# Sheet1.net
KiCad netlist of a schematic drawn in Altium Designer
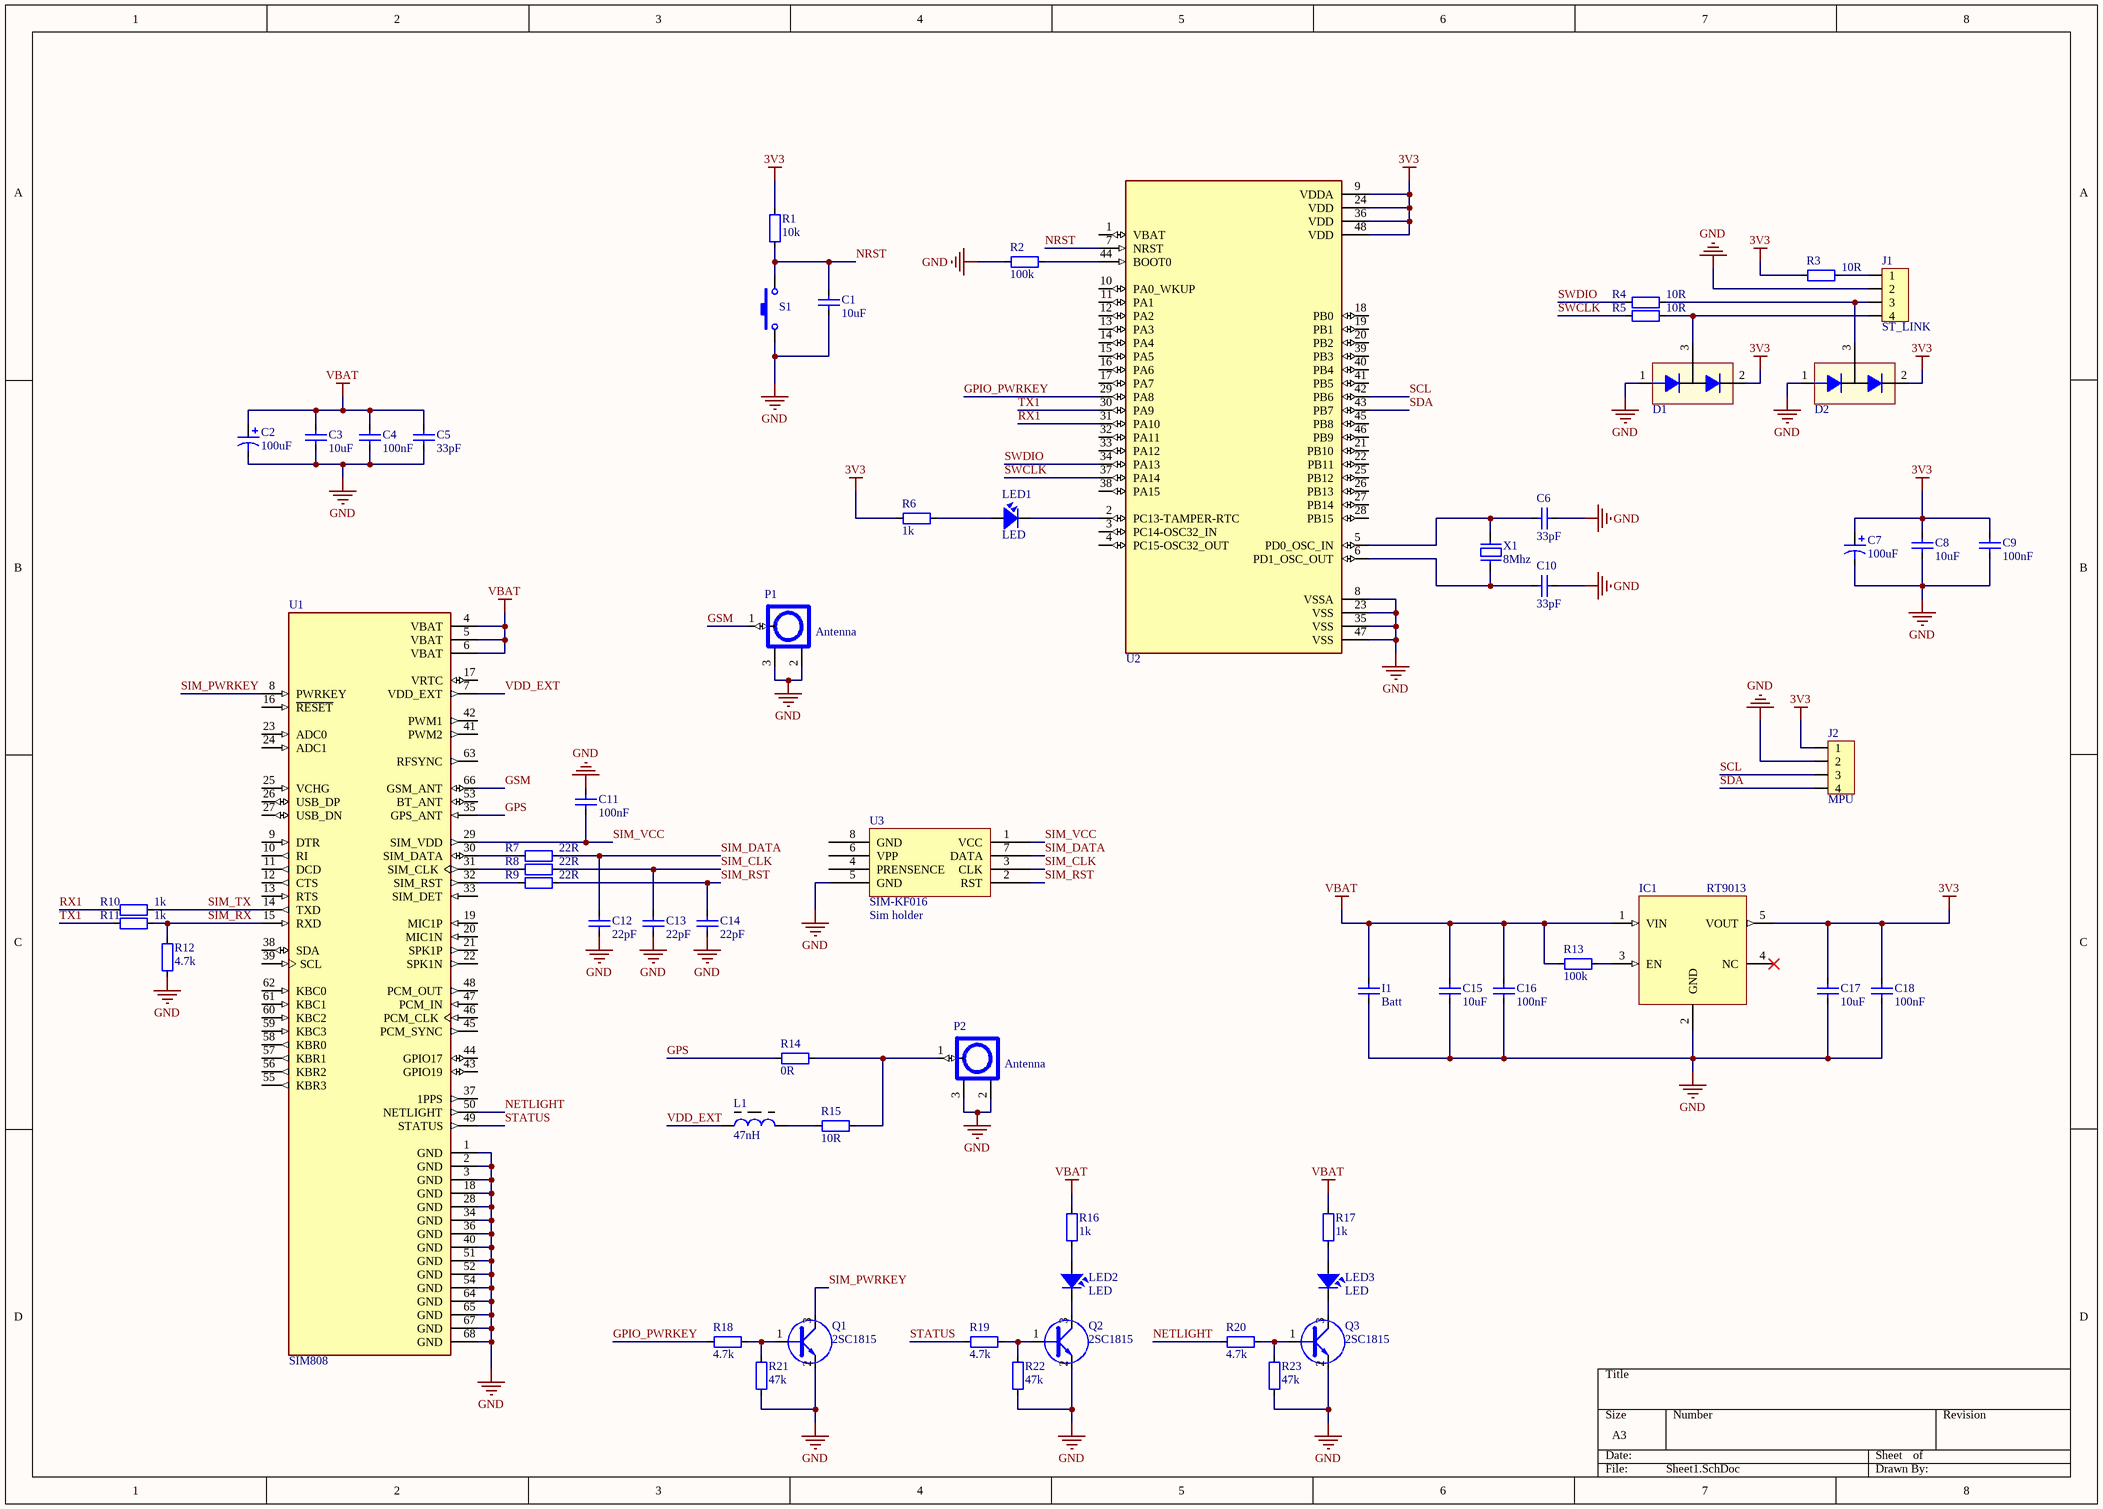
[diagram p0: Sheet1.SchDoc]

(export (version "E")
  (design (tool "Eeschema 10.0.6"))
  (components
    (comp (ref "C1")
      (value "10uF")
      (footprint "CAP_0603")
      (description "Capacitor")
      (fields (field (name "PUBLISHER") "Altium Limited"))
      (libsource (lib "My Library") (part "CapSMD"))
    )
    (comp (ref "C2")
      (value "100uF")
      (footprint "CAP_7343")
      (description "Tantalum")
      (fields (field (name "PUBLISHER") "Altium Limited"))
      (libsource (lib "My Library") (part "Cap Pol"))
    )
    (comp (ref "C3")
      (value "10uF")
      (footprint "CAP_0603")
      (description "Capacitor")
      (fields (field (name "PUBLISHER") "Altium Limited"))
      (libsource (lib "My Library") (part "CapSMD"))
    )
    (comp (ref "C4")
      (value "100nF")
      (footprint "CAP_0603")
      (description "Capacitor")
      (fields (field (name "PUBLISHER") "Altium Limited"))
      (libsource (lib "My Library") (part "CapSMD"))
    )
    (comp (ref "C5")
      (value "33pF")
      (footprint "CAP_0603")
      (description "Capacitor")
      (fields (field (name "PUBLISHER") "Altium Limited"))
      (libsource (lib "My Library") (part "CapSMD"))
    )
    (comp (ref "C6")
      (value "33pF")
      (footprint "CAP_0603")
      (description "Capacitor")
      (fields (field (name "PUBLISHER") "Altium Limited"))
      (libsource (lib "My Library") (part "CapSMD"))
    )
    (comp (ref "C7")
      (value "100uF")
      (footprint "CAP_7343")
      (description "Tantalum")
      (fields (field (name "PUBLISHER") "Altium Limited"))
      (libsource (lib "My Library") (part "Cap Pol"))
    )
    (comp (ref "C8")
      (value "10uF")
      (footprint "CAP_0603")
      (description "Capacitor")
      (fields (field (name "PUBLISHER") "Altium Limited"))
      (libsource (lib "My Library") (part "CapSMD"))
    )
    (comp (ref "C9")
      (value "100nF")
      (footprint "CAP_0603")
      (description "Capacitor")
      (fields (field (name "PUBLISHER") "Altium Limited"))
      (libsource (lib "My Library") (part "CapSMD"))
    )
    (comp (ref "C10")
      (value "33pF")
      (footprint "CAP_0603")
      (description "Capacitor")
      (fields (field (name "PUBLISHER") "Altium Limited"))
      (libsource (lib "My Library") (part "CapSMD"))
    )
    (comp (ref "C11")
      (value "100nF")
      (footprint "CAP_0603")
      (description "Capacitor")
      (fields (field (name "PUBLISHER") "Altium Limited"))
      (libsource (lib "My Library") (part "CapSMD"))
    )
    (comp (ref "C12")
      (value "22pF")
      (footprint "CAP_0603")
      (description "Capacitor")
      (fields (field (name "PUBLISHER") "Altium Limited"))
      (libsource (lib "My Library") (part "CapSMD"))
    )
    (comp (ref "C13")
      (value "22pF")
      (footprint "CAP_0603")
      (description "Capacitor")
      (fields (field (name "PUBLISHER") "Altium Limited"))
      (libsource (lib "My Library") (part "CapSMD"))
    )
    (comp (ref "C14")
      (value "22pF")
      (footprint "CAP_0603")
      (description "Capacitor")
      (fields (field (name "PUBLISHER") "Altium Limited"))
      (libsource (lib "My Library") (part "CapSMD"))
    )
    (comp (ref "C15")
      (value "10uF")
      (footprint "CAP_0603")
      (description "Capacitor")
      (fields (field (name "PUBLISHER") "Altium Limited"))
      (libsource (lib "My Library") (part "CapSMD"))
    )
    (comp (ref "C16")
      (value "100nF")
      (footprint "CAP_0603")
      (description "Capacitor")
      (fields (field (name "PUBLISHER") "Altium Limited"))
      (libsource (lib "My Library") (part "CapSMD"))
    )
    (comp (ref "C17")
      (value "10uF")
      (footprint "CAP_0603")
      (description "Capacitor")
      (fields (field (name "PUBLISHER") "Altium Limited"))
      (libsource (lib "My Library") (part "CapSMD"))
    )
    (comp (ref "C18")
      (value "100nF")
      (footprint "CAP_0603")
      (description "Capacitor")
      (fields (field (name "PUBLISHER") "Altium Limited"))
      (libsource (lib "My Library") (part "CapSMD"))
    )
    (comp (ref "D1")
      (value "DIODE-BAV99")
      (footprint "SOT23")
      (description "ZENER, SOT23,")
      (fields
        (field (name "MANUFACTURER") "ON Semiconductor / Fairchild")
        (field (name "MANUFACTURER PART NUMBER") "BAV99")
        (field (name ".CREATOR") "LeKhaLinh")
        (field (name ".CHECKPCB") "LeKhaLinh")
        (field (name ".CHECKSCH") "LeKhaLinh")
      )
      (libsource (lib "GPS_Traking_V1_1") (part "DIODE-BAV99"))
    )
    (comp (ref "D2")
      (value "DIODE-BAV99")
      (footprint "SOT23")
      (description "ZENER, SOT23,")
      (fields
        (field (name "MANUFACTURER") "ON Semiconductor / Fairchild")
        (field (name "MANUFACTURER PART NUMBER") "BAV99")
        (field (name ".CREATOR") "LeKhaLinh")
        (field (name ".CHECKPCB") "LeKhaLinh")
        (field (name ".CHECKSCH") "LeKhaLinh")
      )
      (libsource (lib "GPS_Traking_V1_1") (part "DIODE-BAV99"))
    )
    (comp (ref "I1")
      (value "Batt")
      (footprint "CAP_3216")
      (description "Pad")
      (fields (field (name "PUBLISHER") "Altium Limited"))
      (libsource (lib "My Library") (part "CapSMD"))
    )
    (comp (ref "IC1")
      (value "RT9013")
      (footprint "SOT23-5")
      (description "RT9013-33GB IC REG LINEAR 3.3V 500mA SOT23-5")
      (libsource (lib "My Library") (part "RT9013"))
    )
    (comp (ref "J1")
      (value "ST_LINK")
      (footprint "JP4-D1T")
      (description "Header IDC, 4 x 1 Pin Vertical 2.54mm Pitch (Non-Boxed, Male)")
      (fields
        (field (name "MANUFACTURER") "Würth Elektronik eiSos GmbH")
        (field (name "PARTNO") "613002143121")
        (field (name "CREATED BY") "Karrer Zheng")
      )
      (libsource (lib "My Library") (part "Header4"))
    )
    (comp (ref "J2")
      (value "MPU")
      (footprint "JP4-D1T")
      (description "Header IDC, 4 x 1 Pin Vertical 2.54mm Pitch (Non-Boxed, Male)")
      (fields
        (field (name "MANUFACTURER") "Würth Elektronik eiSos GmbH")
        (field (name "PARTNO") "613002143121")
        (field (name "CREATED BY") "Karrer Zheng")
      )
      (libsource (lib "My Library") (part "Header4"))
    )
    (comp (ref "L1")
      (value "47nH")
      (footprint "L-0805")
      (description "Inductor")
      (libsource (lib "My Library") (part "Inductor Ferit"))
    )
    (comp (ref "LED1")
      (value "LED")
      (footprint "LED-0805-Orange")
      (description "LED Single colour Green and Red")
      (libsource (lib "My Library") (part "LED"))
    )
    (comp (ref "LED2")
      (value "LED")
      (footprint "LED-0805-Yellow")
      (description "LED Single colour Green and Red")
      (libsource (lib "My Library") (part "LED"))
    )
    (comp (ref "LED3")
      (value "LED")
      (footprint "LED-0805-Red")
      (description "LED Single colour Green and Red")
      (libsource (lib "My Library") (part "LED"))
    )
    (comp (ref "P1")
      (value "Antenna")
      (footprint "IPXS")
      (description "Antenna GSM GPS")
      (libsource (lib "My Library") (part "IPXSx66"))
    )
    (comp (ref "P2")
      (value "Antenna")
      (footprint "IPXS")
      (description "Antenna GSM GPS")
      (libsource (lib "My Library") (part "IPXSx66"))
    )
    (comp (ref "Q1")
      (value "2SC1815")
      (footprint "SOT23D")
      (description "NPN 600mW, ECB")
      (libsource (lib "My Library") (part "2SC1815"))
    )
    (comp (ref "Q2")
      (value "2SC1815")
      (footprint "SOT23D")
      (description "NPN 600mW, ECB")
      (libsource (lib "My Library") (part "2SC1815"))
    )
    (comp (ref "Q3")
      (value "2SC1815")
      (footprint "SOT23D")
      (description "NPN 600mW, ECB")
      (libsource (lib "My Library") (part "2SC1815"))
    )
    (comp (ref "R1")
      (value "10k")
      (footprint "RES-SMD-0603")
      (description "Resistor")
      (fields
        (field (name "MANUFACTURER") "Generic Components")
        (field (name "PUBLISHER") "Altium Hobart Technology Centre")
      )
      (libsource (lib "My Library") (part "Resistor - SMD"))
    )
    (comp (ref "R2")
      (value "100k")
      (footprint "RES-SMD-0603")
      (description "Resistor")
      (fields
        (field (name "MANUFACTURER") "Generic Components")
        (field (name "PUBLISHER") "Altium Hobart Technology Centre")
      )
      (libsource (lib "My Library") (part "Resistor - SMD"))
    )
    (comp (ref "R3")
      (value "10R")
      (footprint "RES-SMD-0603")
      (description "Resistor")
      (fields
        (field (name "MANUFACTURER") "Generic Components")
        (field (name "PUBLISHER") "Altium Hobart Technology Centre")
      )
      (libsource (lib "My Library") (part "Resistor - SMD"))
    )
    (comp (ref "R4")
      (value "10R")
      (footprint "RES-SMD-0603")
      (description "Resistor")
      (fields
        (field (name "MANUFACTURER") "Generic Components")
        (field (name "PUBLISHER") "Altium Hobart Technology Centre")
      )
      (libsource (lib "My Library") (part "Resistor - SMD"))
    )
    (comp (ref "R5")
      (value "10R")
      (footprint "RES-SMD-0603")
      (description "Resistor")
      (fields
        (field (name "MANUFACTURER") "Generic Components")
        (field (name "PUBLISHER") "Altium Hobart Technology Centre")
      )
      (libsource (lib "My Library") (part "Resistor - SMD"))
    )
    (comp (ref "R6")
      (value "1k")
      (footprint "RES-SMD-0603")
      (description "Resistor")
      (fields
        (field (name "MANUFACTURER") "Generic Components")
        (field (name "PUBLISHER") "Altium Hobart Technology Centre")
      )
      (libsource (lib "My Library") (part "Resistor - SMD"))
    )
    (comp (ref "R7")
      (value "22R")
      (footprint "RES-SMD-0603")
      (description "Resistor")
      (fields
        (field (name "MANUFACTURER") "Generic Components")
        (field (name "PUBLISHER") "Altium Hobart Technology Centre")
      )
      (libsource (lib "My Library") (part "Resistor - SMD"))
    )
    (comp (ref "R8")
      (value "22R")
      (footprint "RES-SMD-0603")
      (description "Resistor")
      (fields
        (field (name "MANUFACTURER") "Generic Components")
        (field (name "PUBLISHER") "Altium Hobart Technology Centre")
      )
      (libsource (lib "My Library") (part "Resistor - SMD"))
    )
    (comp (ref "R9")
      (value "22R")
      (footprint "RES-SMD-0603")
      (description "Resistor")
      (fields
        (field (name "MANUFACTURER") "Generic Components")
        (field (name "PUBLISHER") "Altium Hobart Technology Centre")
      )
      (libsource (lib "My Library") (part "Resistor - SMD"))
    )
    (comp (ref "R10")
      (value "1k")
      (footprint "RES-SMD-0603")
      (description "Resistor")
      (fields
        (field (name "MANUFACTURER") "Generic Components")
        (field (name "PUBLISHER") "Altium Hobart Technology Centre")
      )
      (libsource (lib "My Library") (part "Resistor - SMD"))
    )
    (comp (ref "R11")
      (value "1k")
      (footprint "RES-SMD-0603")
      (description "Resistor")
      (fields
        (field (name "MANUFACTURER") "Generic Components")
        (field (name "PUBLISHER") "Altium Hobart Technology Centre")
      )
      (libsource (lib "My Library") (part "Resistor - SMD"))
    )
    (comp (ref "R12")
      (value "4.7k")
      (footprint "RES-SMD-0603")
      (description "Resistor")
      (fields
        (field (name "MANUFACTURER") "Generic Components")
        (field (name "PUBLISHER") "Altium Hobart Technology Centre")
      )
      (libsource (lib "My Library") (part "Resistor - SMD"))
    )
    (comp (ref "R13")
      (value "100k")
      (footprint "RES-SMD-0603")
      (description "Resistor")
      (fields
        (field (name "MANUFACTURER") "Generic Components")
        (field (name "PUBLISHER") "Altium Hobart Technology Centre")
      )
      (libsource (lib "My Library") (part "Resistor - SMD"))
    )
    (comp (ref "R14")
      (value "0R")
      (footprint "RES-SMD-0805")
      (description "Resistor")
      (fields
        (field (name "MANUFACTURER") "Generic Components")
        (field (name "PUBLISHER") "Altium Hobart Technology Centre")
      )
      (libsource (lib "My Library") (part "Resistor - SMD"))
    )
    (comp (ref "R15")
      (value "10R")
      (footprint "RES-SMD-0805")
      (description "Resistor")
      (fields
        (field (name "MANUFACTURER") "Generic Components")
        (field (name "PUBLISHER") "Altium Hobart Technology Centre")
      )
      (libsource (lib "My Library") (part "Resistor - SMD"))
    )
    (comp (ref "R16")
      (value "1k")
      (footprint "RES-SMD-0603")
      (description "Resistor")
      (fields
        (field (name "MANUFACTURER") "Generic Components")
        (field (name "PUBLISHER") "Altium Hobart Technology Centre")
      )
      (libsource (lib "My Library") (part "Resistor - SMD"))
    )
    (comp (ref "R17")
      (value "1k")
      (footprint "RES-SMD-0603")
      (description "Resistor")
      (fields
        (field (name "MANUFACTURER") "Generic Components")
        (field (name "PUBLISHER") "Altium Hobart Technology Centre")
      )
      (libsource (lib "My Library") (part "Resistor - SMD"))
    )
    (comp (ref "R18")
      (value "4.7k")
      (footprint "RES-SMD-0603")
      (description "Resistor")
      (fields
        (field (name "MANUFACTURER") "Generic Components")
        (field (name "PUBLISHER") "Altium Hobart Technology Centre")
      )
      (libsource (lib "My Library") (part "Resistor - SMD"))
    )
    (comp (ref "R19")
      (value "4.7k")
      (footprint "RES-SMD-0603")
      (description "Resistor")
      (fields
        (field (name "MANUFACTURER") "Generic Components")
        (field (name "PUBLISHER") "Altium Hobart Technology Centre")
      )
      (libsource (lib "My Library") (part "Resistor - SMD"))
    )
    (comp (ref "R20")
      (value "4.7k")
      (footprint "RES-SMD-0603")
      (description "Resistor")
      (fields
        (field (name "MANUFACTURER") "Generic Components")
        (field (name "PUBLISHER") "Altium Hobart Technology Centre")
      )
      (libsource (lib "My Library") (part "Resistor - SMD"))
    )
    (comp (ref "R21")
      (value "47k")
      (footprint "RES-SMD-0603")
      (description "Resistor")
      (fields
        (field (name "MANUFACTURER") "Generic Components")
        (field (name "PUBLISHER") "Altium Hobart Technology Centre")
      )
      (libsource (lib "My Library") (part "Resistor - SMD"))
    )
    (comp (ref "R22")
      (value "47k")
      (footprint "RES-SMD-0603")
      (description "Resistor")
      (fields
        (field (name "MANUFACTURER") "Generic Components")
        (field (name "PUBLISHER") "Altium Hobart Technology Centre")
      )
      (libsource (lib "My Library") (part "Resistor - SMD"))
    )
    (comp (ref "R23")
      (value "47k")
      (footprint "RES-SMD-0603")
      (description "Resistor")
      (fields
        (field (name "MANUFACTURER") "Generic Components")
        (field (name "PUBLISHER") "Altium Hobart Technology Centre")
      )
      (libsource (lib "My Library") (part "Resistor - SMD"))
    )
    (comp (ref "S1")
      (value "SW-SMD")
      (footprint "SW 3x2x4")
      (description "Switch")
      (fields (field (name "PUBLISHER") "Altium Limited"))
      (libsource (lib "My Library") (part "SW-SMD"))
    )
    (comp (ref "U1")
      (value "SIM808")
      (footprint "XCVR_SIM808")
      (description "SIM808 GPS, GPRS/GSM RF Arduino Platform Evaluation Expansion Board")
      (fields (field (name "MF") "Adafruit Industries"))
      (libsource (lib "My Library") (part "SIM808"))
    )
    (comp (ref "U2")
      (value "STM32")
      (footprint "LQFP 48")
      (description "STM32 ARM-based 32-bit MCU with 64 Kbytes Flash, 64-pin LQFP, Industrial Temperature")
      (libsource (lib "My Library") (part "STM32F103C8T6"))
    )
    (comp (ref "U3")
      (value "SIM-KF016")
      (footprint "Sim Socket")
      (description "SIM Card Holder KF-016")
      (fields (field (name "ALTIUM_VALUE") "Sim holder"))
      (libsource (lib "My Library") (part "Sim holder"))
    )
    (comp (ref "X1")
      (value "8Mhz")
      (footprint "XTAL 5032 SMD")
      (description "Crystal For all Crystal 2pin.")
      (libsource (lib "My Library") (part "XT2"))
    )
  )
  (nets
    (net (code "1") (name "/GPIO_PWRKEY") (class "Default")
      (node (ref "R18") (pin "1") (pinfunction "1_1") (pintype "passive"))
      (node (ref "U2") (pin "29") (pinfunction "PA8_29") (pintype "bidirectional"))
    )
    (net (code "2") (name "/GPS") (class "Default")
      (node (ref "R14") (pin "1") (pinfunction "1_1") (pintype "passive"))
      (node (ref "U1") (pin "35") (pinfunction "GPS_ANT_35") (pintype "input"))
    )
    (net (code "3") (name "/GSM") (class "Default")
      (node (ref "P1") (pin "1") (pintype "bidirectional"))
      (node (ref "U1") (pin "66") (pinfunction "GSM_ANT_66") (pintype "bidirectional"))
    )
    (net (code "4") (name "/NETLIGHT") (class "Default")
      (node (ref "R20") (pin "1") (pinfunction "1_1") (pintype "passive"))
      (node (ref "U1") (pin "50") (pinfunction "NETLIGHT_50") (pintype "output"))
    )
    (net (code "5") (name "/NRST") (class "Default")
      (node (ref "C1") (pin "2") (pinfunction "2_2") (pintype "passive"))
      (node (ref "R1") (pin "1") (pinfunction "1_1") (pintype "passive"))
      (node (ref "S1") (pin "2") (pinfunction "2_2") (pintype "passive"))
      (node (ref "U2") (pin "7") (pinfunction "NRST_7") (pintype "input"))
    )
    (net (code "6") (name "/RX1") (class "Default")
      (node (ref "R10") (pin "2") (pinfunction "2_2") (pintype "passive"))
      (node (ref "U2") (pin "31") (pinfunction "PA10_31") (pintype "bidirectional"))
    )
    (net (code "7") (name "/SCL") (class "Default")
      (node (ref "J2") (pin "3") (pinfunction "3_3") (pintype "passive"))
      (node (ref "U2") (pin "42") (pinfunction "PB6_42") (pintype "bidirectional"))
    )
    (net (code "8") (name "/SDA") (class "Default")
      (node (ref "J2") (pin "4") (pinfunction "4_4") (pintype "passive"))
      (node (ref "U2") (pin "43") (pinfunction "PB7_43") (pintype "bidirectional"))
    )
    (net (code "9") (name "/SIM_CLK") (class "Default")
      (node (ref "C13") (pin "1") (pinfunction "1_1") (pintype "passive"))
      (node (ref "R8") (pin "1") (pinfunction "1_1") (pintype "passive"))
      (node (ref "U3") (pin "3") (pinfunction "CLK_3") (pintype "passive"))
    )
    (net (code "10") (name "/SIM_DATA") (class "Default")
      (node (ref "C12") (pin "1") (pinfunction "1_1") (pintype "passive"))
      (node (ref "R7") (pin "1") (pinfunction "1_1") (pintype "passive"))
      (node (ref "U3") (pin "7") (pinfunction "DATA_7") (pintype "passive"))
    )
    (net (code "11") (name "/SIM_PWRKEY") (class "Default")
      (node (ref "Q1") (pin "3") (pinfunction "C_3") (pintype "passive"))
      (node (ref "U1") (pin "8") (pinfunction "PWRKEY_8") (pintype "input"))
    )
    (net (code "12") (name "/SIM_RST") (class "Default")
      (node (ref "C14") (pin "1") (pinfunction "1_1") (pintype "passive"))
      (node (ref "R9") (pin "1") (pinfunction "1_1") (pintype "passive"))
      (node (ref "U3") (pin "2") (pinfunction "RST_2") (pintype "passive"))
    )
    (net (code "13") (name "/SIM_RX") (class "Default")
      (node (ref "R11") (pin "1") (pinfunction "1_1") (pintype "passive"))
      (node (ref "R12") (pin "1") (pinfunction "1_1") (pintype "passive"))
      (node (ref "U1") (pin "15") (pinfunction "RXD_15") (pintype "input"))
    )
    (net (code "14") (name "/SIM_TX") (class "Default")
      (node (ref "R10") (pin "1") (pinfunction "1_1") (pintype "passive"))
      (node (ref "U1") (pin "14") (pinfunction "TXD_14") (pintype "output"))
    )
    (net (code "15") (name "/SIM_VCC") (class "Default")
      (node (ref "C11") (pin "2") (pinfunction "2_2") (pintype "passive"))
      (node (ref "U1") (pin "29") (pinfunction "SIM_VDD_29") (pintype "output"))
      (node (ref "U3") (pin "1") (pinfunction "VCC_1") (pintype "passive"))
    )
    (net (code "16") (name "/STATUS") (class "Default")
      (node (ref "R19") (pin "1") (pinfunction "1_1") (pintype "passive"))
      (node (ref "U1") (pin "49") (pinfunction "STATUS_49") (pintype "output"))
    )
    (net (code "17") (name "/SWCLK") (class "Default")
      (node (ref "R5") (pin "1") (pinfunction "1_1") (pintype "passive"))
      (node (ref "U2") (pin "37") (pinfunction "PA14_37") (pintype "bidirectional"))
    )
    (net (code "18") (name "/SWDIO") (class "Default")
      (node (ref "R4") (pin "1") (pinfunction "1_1") (pintype "passive"))
      (node (ref "U2") (pin "34") (pinfunction "PA13_34") (pintype "bidirectional"))
    )
    (net (code "19") (name "/TX1") (class "Default")
      (node (ref "R11") (pin "2") (pinfunction "2_2") (pintype "passive"))
      (node (ref "U2") (pin "30") (pinfunction "PA9_30") (pintype "bidirectional"))
    )
    (net (code "20") (name "/VDD_EXT") (class "Default")
      (node (ref "L1") (pin "1") (pinfunction "1_1") (pintype "passive"))
      (node (ref "U1") (pin "7") (pinfunction "VDD_EXT_7") (pintype "output"))
    )
    (net (code "21") (name "3V3") (class "Default")
      (node (ref "C17") (pin "2") (pinfunction "2_2") (pintype "passive"))
      (node (ref "C18") (pin "2") (pinfunction "2_2") (pintype "passive"))
      (node (ref "C7") (pin "1") (pinfunction "1_1") (pintype "passive"))
      (node (ref "C8") (pin "2") (pinfunction "2_2") (pintype "passive"))
      (node (ref "C9") (pin "2") (pinfunction "2_2") (pintype "passive"))
      (node (ref "D1") (pin "2") (pinfunction "2_2") (pintype "passive"))
      (node (ref "D2") (pin "2") (pinfunction "2_2") (pintype "passive"))
      (node (ref "IC1") (pin "5") (pinfunction "VOUT_5") (pintype "output"))
      (node (ref "J2") (pin "1") (pinfunction "1_1") (pintype "passive"))
      (node (ref "R1") (pin "2") (pinfunction "2_2") (pintype "passive"))
      (node (ref "R3") (pin "1") (pinfunction "1_1") (pintype "passive"))
      (node (ref "R6") (pin "1") (pinfunction "1_1") (pintype "passive"))
      (node (ref "U2") (pin "24") (pinfunction "VDD_24") (pintype "power_in"))
      (node (ref "U2") (pin "36") (pinfunction "VDD_36") (pintype "power_in"))
      (node (ref "U2") (pin "48") (pinfunction "VDD_48") (pintype "power_in"))
      (node (ref "U2") (pin "9") (pinfunction "VDDA_9") (pintype "power_in"))
    )
    (net (code "22") (name "GND") (class "Default")
      (node (ref "C1") (pin "1") (pinfunction "1_1") (pintype "passive"))
      (node (ref "C10") (pin "2") (pinfunction "2_2") (pintype "passive"))
      (node (ref "C11") (pin "1") (pinfunction "1_1") (pintype "passive"))
      (node (ref "C12") (pin "2") (pinfunction "2_2") (pintype "passive"))
      (node (ref "C13") (pin "2") (pinfunction "2_2") (pintype "passive"))
      (node (ref "C14") (pin "2") (pinfunction "2_2") (pintype "passive"))
      (node (ref "C15") (pin "1") (pinfunction "1_1") (pintype "passive"))
      (node (ref "C16") (pin "1") (pinfunction "1_1") (pintype "passive"))
      (node (ref "C17") (pin "1") (pinfunction "1_1") (pintype "passive"))
      (node (ref "C18") (pin "1") (pinfunction "1_1") (pintype "passive"))
      (node (ref "C2") (pin "2") (pinfunction "2_2") (pintype "passive"))
      (node (ref "C3") (pin "1") (pinfunction "1_1") (pintype "passive"))
      (node (ref "C4") (pin "1") (pinfunction "1_1") (pintype "passive"))
      (node (ref "C5") (pin "1") (pinfunction "1_1") (pintype "passive"))
      (node (ref "C6") (pin "2") (pinfunction "2_2") (pintype "passive"))
      (node (ref "C7") (pin "2") (pinfunction "2_2") (pintype "passive"))
      (node (ref "C8") (pin "1") (pinfunction "1_1") (pintype "passive"))
      (node (ref "C9") (pin "1") (pinfunction "1_1") (pintype "passive"))
      (node (ref "D1") (pin "1") (pinfunction "1_1") (pintype "passive"))
      (node (ref "D2") (pin "1") (pinfunction "1_1") (pintype "passive"))
      (node (ref "I1") (pin "1") (pinfunction "1_1") (pintype "passive"))
      (node (ref "IC1") (pin "2") (pinfunction "GND_2") (pintype "passive"))
      (node (ref "J1") (pin "2") (pinfunction "2_2") (pintype "passive"))
      (node (ref "J2") (pin "2") (pinfunction "2_2") (pintype "passive"))
      (node (ref "P1") (pin "2") (pintype "passive"))
      (node (ref "P1") (pin "3") (pintype "passive"))
      (node (ref "P2") (pin "2") (pintype "passive"))
      (node (ref "P2") (pin "3") (pintype "passive"))
      (node (ref "Q1") (pin "2") (pinfunction "E_2") (pintype "passive"))
      (node (ref "Q2") (pin "2") (pinfunction "E_2") (pintype "passive"))
      (node (ref "Q3") (pin "2") (pinfunction "E_2") (pintype "passive"))
      (node (ref "R12") (pin "2") (pinfunction "2_2") (pintype "passive"))
      (node (ref "R2") (pin "2") (pinfunction "2_2") (pintype "passive"))
      (node (ref "R21") (pin "1") (pinfunction "1_1") (pintype "passive"))
      (node (ref "R22") (pin "1") (pinfunction "1_1") (pintype "passive"))
      (node (ref "R23") (pin "1") (pinfunction "1_1") (pintype "passive"))
      (node (ref "S1") (pin "1") (pinfunction "1_1") (pintype "passive"))
      (node (ref "U1") (pin "1") (pinfunction "GND_1") (pintype "power_in"))
      (node (ref "U1") (pin "18") (pinfunction "GND_18") (pintype "power_in"))
      (node (ref "U1") (pin "2") (pinfunction "GND_2") (pintype "power_in"))
      (node (ref "U1") (pin "28") (pinfunction "GND_28") (pintype "power_in"))
      (node (ref "U1") (pin "3") (pinfunction "GND_3") (pintype "power_in"))
      (node (ref "U1") (pin "34") (pinfunction "GND_34") (pintype "power_in"))
      (node (ref "U1") (pin "36") (pinfunction "GND_36") (pintype "power_in"))
      (node (ref "U1") (pin "40") (pinfunction "GND_40") (pintype "power_in"))
      (node (ref "U1") (pin "51") (pinfunction "GND_51") (pintype "power_in"))
      (node (ref "U1") (pin "52") (pinfunction "GND_52") (pintype "power_in"))
      (node (ref "U1") (pin "54") (pinfunction "GND_54") (pintype "power_in"))
      (node (ref "U1") (pin "64") (pinfunction "GND_64") (pintype "power_in"))
      (node (ref "U1") (pin "65") (pinfunction "GND_65") (pintype "power_in"))
      (node (ref "U1") (pin "67") (pinfunction "GND_67") (pintype "power_in"))
      (node (ref "U1") (pin "68") (pinfunction "GND_68") (pintype "power_in"))
      (node (ref "U2") (pin "23") (pinfunction "VSS_23") (pintype "power_in"))
      (node (ref "U2") (pin "35") (pinfunction "VSS_35") (pintype "power_in"))
      (node (ref "U2") (pin "47") (pinfunction "VSS_47") (pintype "power_in"))
      (node (ref "U2") (pin "8") (pinfunction "VSSA_8") (pintype "power_in"))
      (node (ref "U3") (pin "5") (pinfunction "GND_5") (pintype "passive"))
    )
    (net (code "23") (name "Net-(D1-Pad3)") (class "Default")
      (node (ref "D1") (pin "3") (pinfunction "3_3") (pintype "passive"))
      (node (ref "J1") (pin "4") (pinfunction "4_4") (pintype "passive"))
      (node (ref "R5") (pin "2") (pinfunction "2_2") (pintype "passive"))
    )
    (net (code "24") (name "Net-(D2-Pad3)") (class "Default")
      (node (ref "D2") (pin "3") (pinfunction "3_3") (pintype "passive"))
      (node (ref "J1") (pin "3") (pinfunction "3_3") (pintype "passive"))
      (node (ref "R4") (pin "2") (pinfunction "2_2") (pintype "passive"))
    )
    (net (code "25") (name "Net-(IC1-EN)") (class "Default")
      (node (ref "IC1") (pin "3") (pinfunction "EN_3") (pintype "input"))
      (node (ref "R13") (pin "1") (pinfunction "1_1") (pintype "passive"))
    )
    (net (code "26") (name "Net-(J1-Pad1)") (class "Default")
      (node (ref "J1") (pin "1") (pinfunction "1_1") (pintype "passive"))
      (node (ref "R3") (pin "2") (pinfunction "2_2") (pintype "passive"))
    )
    (net (code "27") (name "Net-(L1-Pad2)") (class "Default")
      (node (ref "L1") (pin "2") (pinfunction "2_2") (pintype "passive"))
      (node (ref "R15") (pin "2") (pinfunction "2_2") (pintype "passive"))
    )
    (net (code "28") (name "Net-(LED1-Pad1)") (class "Default")
      (node (ref "LED1") (pin "1") (pinfunction "1_1") (pintype "passive"))
      (node (ref "R6") (pin "2") (pinfunction "2_2") (pintype "passive"))
    )
    (net (code "29") (name "Net-(LED2-Pad1)") (class "Default")
      (node (ref "LED2") (pin "1") (pinfunction "1_1") (pintype "passive"))
      (node (ref "R16") (pin "1") (pinfunction "1_1") (pintype "passive"))
    )
    (net (code "30") (name "Net-(LED3-Pad1)") (class "Default")
      (node (ref "LED3") (pin "1") (pinfunction "1_1") (pintype "passive"))
      (node (ref "R17") (pin "1") (pinfunction "1_1") (pintype "passive"))
    )
    (net (code "31") (name "Net-(P2-Pad1)") (class "Default")
      (node (ref "P2") (pin "1") (pintype "bidirectional"))
      (node (ref "R14") (pin "2") (pinfunction "2_2") (pintype "passive"))
      (node (ref "R15") (pin "1") (pinfunction "1_1") (pintype "passive"))
    )
    (net (code "32") (name "Net-(Q1-B)") (class "Default")
      (node (ref "Q1") (pin "1") (pinfunction "B_1") (pintype "passive"))
      (node (ref "R18") (pin "2") (pinfunction "2_2") (pintype "passive"))
      (node (ref "R21") (pin "2") (pinfunction "2_2") (pintype "passive"))
    )
    (net (code "33") (name "Net-(Q2-B)") (class "Default")
      (node (ref "Q2") (pin "1") (pinfunction "B_1") (pintype "passive"))
      (node (ref "R19") (pin "2") (pinfunction "2_2") (pintype "passive"))
      (node (ref "R22") (pin "2") (pinfunction "2_2") (pintype "passive"))
    )
    (net (code "34") (name "Net-(Q2-C)") (class "Default")
      (node (ref "LED2") (pin "2") (pinfunction "2_2") (pintype "passive"))
      (node (ref "Q2") (pin "3") (pinfunction "C_3") (pintype "passive"))
    )
    (net (code "35") (name "Net-(Q3-B)") (class "Default")
      (node (ref "Q3") (pin "1") (pinfunction "B_1") (pintype "passive"))
      (node (ref "R20") (pin "2") (pinfunction "2_2") (pintype "passive"))
      (node (ref "R23") (pin "2") (pinfunction "2_2") (pintype "passive"))
    )
    (net (code "36") (name "Net-(Q3-C)") (class "Default")
      (node (ref "LED3") (pin "2") (pinfunction "2_2") (pintype "passive"))
      (node (ref "Q3") (pin "3") (pinfunction "C_3") (pintype "passive"))
    )
    (net (code "37") (name "Net-(U1-SIM_CLK)") (class "Default")
      (node (ref "R8") (pin "2") (pinfunction "2_2") (pintype "passive"))
      (node (ref "U1") (pin "31") (pinfunction "SIM_CLK_31") (pintype "output"))
    )
    (net (code "38") (name "Net-(U1-SIM_DATA)") (class "Default")
      (node (ref "R7") (pin "2") (pinfunction "2_2") (pintype "passive"))
      (node (ref "U1") (pin "30") (pinfunction "SIM_DATA_30") (pintype "bidirectional"))
    )
    (net (code "39") (name "Net-(U1-SIM_RST)") (class "Default")
      (node (ref "R9") (pin "2") (pinfunction "2_2") (pintype "passive"))
      (node (ref "U1") (pin "32") (pinfunction "SIM_RST_32") (pintype "output"))
    )
    (net (code "40") (name "Net-(U2-BOOT0)") (class "Default")
      (node (ref "R2") (pin "1") (pinfunction "1_1") (pintype "passive"))
      (node (ref "U2") (pin "44") (pinfunction "BOOT0_44") (pintype "input"))
    )
    (net (code "41") (name "Net-(U2-PC13-TAMPER-RTC)") (class "Default")
      (node (ref "LED1") (pin "2") (pinfunction "2_2") (pintype "passive"))
      (node (ref "U2") (pin "2") (pinfunction "PC13-TAMPER-RTC_2") (pintype "bidirectional"))
    )
    (net (code "42") (name "Net-(U2-PD0_OSC_IN)") (class "Default")
      (node (ref "C6") (pin "1") (pinfunction "1_1") (pintype "passive"))
      (node (ref "U2") (pin "5") (pinfunction "PD0_OSC_IN_5") (pintype "bidirectional"))
      (node (ref "X1") (pin "2") (pinfunction "2_2") (pintype "passive"))
    )
    (net (code "43") (name "Net-(U2-PD1_OSC_OUT)") (class "Default")
      (node (ref "C10") (pin "1") (pinfunction "1_1") (pintype "passive"))
      (node (ref "U2") (pin "6") (pinfunction "PD1_OSC_OUT_6") (pintype "bidirectional"))
      (node (ref "X1") (pin "1") (pinfunction "1_1") (pintype "passive"))
    )
    (net (code "44") (name "VBAT") (class "Default")
      (node (ref "C15") (pin "2") (pinfunction "2_2") (pintype "passive"))
      (node (ref "C16") (pin "2") (pinfunction "2_2") (pintype "passive"))
      (node (ref "C2") (pin "1") (pinfunction "1_1") (pintype "passive"))
      (node (ref "C3") (pin "2") (pinfunction "2_2") (pintype "passive"))
      (node (ref "C4") (pin "2") (pinfunction "2_2") (pintype "passive"))
      (node (ref "C5") (pin "2") (pinfunction "2_2") (pintype "passive"))
      (node (ref "I1") (pin "2") (pinfunction "2_2") (pintype "passive"))
      (node (ref "IC1") (pin "1") (pinfunction "VIN_1") (pintype "input"))
      (node (ref "R13") (pin "2") (pinfunction "2_2") (pintype "passive"))
      (node (ref "R16") (pin "2") (pinfunction "2_2") (pintype "passive"))
      (node (ref "R17") (pin "2") (pinfunction "2_2") (pintype "passive"))
      (node (ref "U1") (pin "4") (pinfunction "VBAT_4") (pintype "power_in"))
      (node (ref "U1") (pin "5") (pinfunction "VBAT_5") (pintype "power_in"))
      (node (ref "U1") (pin "6") (pinfunction "VBAT_6") (pintype "power_in"))
    )
    (net (code "45") (name "unconnected-(IC1-NC-Pad4)") (class "Default")
      (node (ref "IC1") (pin "4") (pinfunction "NC_4") (pintype "passive+no_connect"))
    )
    (net (code "46") (name "unconnected-(U1-1PPS-Pad37)") (class "Default")
      (node (ref "U1") (pin "37") (pinfunction "1PPS_37") (pintype "output"))
    )
    (net (code "47") (name "unconnected-(U1-ADC0-Pad23)") (class "Default")
      (node (ref "U1") (pin "23") (pinfunction "ADC0_23") (pintype "input"))
    )
    (net (code "48") (name "unconnected-(U1-ADC1-Pad24)") (class "Default")
      (node (ref "U1") (pin "24") (pinfunction "ADC1_24") (pintype "input"))
    )
    (net (code "49") (name "unconnected-(U1-BT_ANT-Pad53)") (class "Default")
      (node (ref "U1") (pin "53") (pinfunction "BT_ANT_53") (pintype "bidirectional"))
    )
    (net (code "50") (name "unconnected-(U1-CTS-Pad12)") (class "Default")
      (node (ref "U1") (pin "12") (pinfunction "CTS_12") (pintype "output"))
    )
    (net (code "51") (name "unconnected-(U1-DCD-Pad11)") (class "Default")
      (node (ref "U1") (pin "11") (pinfunction "DCD_11") (pintype "output"))
    )
    (net (code "52") (name "unconnected-(U1-DTR-Pad9)") (class "Default")
      (node (ref "U1") (pin "9") (pinfunction "DTR_9") (pintype "input"))
    )
    (net (code "53") (name "unconnected-(U1-GPIO17-Pad44)") (class "Default")
      (node (ref "U1") (pin "44") (pinfunction "GPIO17_44") (pintype "bidirectional"))
    )
    (net (code "54") (name "unconnected-(U1-GPIO19-Pad43)") (class "Default")
      (node (ref "U1") (pin "43") (pinfunction "GPIO19_43") (pintype "bidirectional"))
    )
    (net (code "55") (name "unconnected-(U1-KBC0-Pad62)") (class "Default")
      (node (ref "U1") (pin "62") (pinfunction "KBC0_62") (pintype "input"))
    )
    (net (code "56") (name "unconnected-(U1-KBC1-Pad61)") (class "Default")
      (node (ref "U1") (pin "61") (pinfunction "KBC1_61") (pintype "input"))
    )
    (net (code "57") (name "unconnected-(U1-KBC2-Pad60)") (class "Default")
      (node (ref "U1") (pin "60") (pinfunction "KBC2_60") (pintype "input"))
    )
    (net (code "58") (name "unconnected-(U1-KBC3-Pad59)") (class "Default")
      (node (ref "U1") (pin "59") (pinfunction "KBC3_59") (pintype "input"))
    )
    (net (code "59") (name "unconnected-(U1-KBR0-Pad58)") (class "Default")
      (node (ref "U1") (pin "58") (pinfunction "KBR0_58") (pintype "output"))
    )
    (net (code "60") (name "unconnected-(U1-KBR1-Pad57)") (class "Default")
      (node (ref "U1") (pin "57") (pinfunction "KBR1_57") (pintype "output"))
    )
    (net (code "61") (name "unconnected-(U1-KBR2-Pad56)") (class "Default")
      (node (ref "U1") (pin "56") (pinfunction "KBR2_56") (pintype "output"))
    )
    (net (code "62") (name "unconnected-(U1-KBR3-Pad55)") (class "Default")
      (node (ref "U1") (pin "55") (pinfunction "KBR3_55") (pintype "output"))
    )
    (net (code "63") (name "unconnected-(U1-MIC1N-Pad20)") (class "Default")
      (node (ref "U1") (pin "20") (pinfunction "MIC1N_20") (pintype "input"))
    )
    (net (code "64") (name "unconnected-(U1-MIC1P-Pad19)") (class "Default")
      (node (ref "U1") (pin "19") (pinfunction "MIC1P_19") (pintype "input"))
    )
    (net (code "65") (name "unconnected-(U1-PCM_CLK-Pad46)") (class "Default")
      (node (ref "U1") (pin "46") (pinfunction "PCM_CLK_46") (pintype "input"))
    )
    (net (code "66") (name "unconnected-(U1-PCM_IN-Pad47)") (class "Default")
      (node (ref "U1") (pin "47") (pinfunction "PCM_IN_47") (pintype "input"))
    )
    (net (code "67") (name "unconnected-(U1-PCM_OUT-Pad48)") (class "Default")
      (node (ref "U1") (pin "48") (pinfunction "PCM_OUT_48") (pintype "output"))
    )
    (net (code "68") (name "unconnected-(U1-PCM_SYNC-Pad45)") (class "Default")
      (node (ref "U1") (pin "45") (pinfunction "PCM_SYNC_45") (pintype "output"))
    )
    (net (code "69") (name "unconnected-(U1-PWM1-Pad42)") (class "Default")
      (node (ref "U1") (pin "42") (pinfunction "PWM1_42") (pintype "output"))
    )
    (net (code "70") (name "unconnected-(U1-PWM2-Pad41)") (class "Default")
      (node (ref "U1") (pin "41") (pinfunction "PWM2_41") (pintype "output"))
    )
    (net (code "71") (name "unconnected-(U1-RFSYNC-Pad63)") (class "Default")
      (node (ref "U1") (pin "63") (pinfunction "RFSYNC_63") (pintype "output"))
    )
    (net (code "72") (name "unconnected-(U1-RI-Pad10)") (class "Default")
      (node (ref "U1") (pin "10") (pinfunction "RI_10") (pintype "output"))
    )
    (net (code "73") (name "unconnected-(U1-RTS-Pad13)") (class "Default")
      (node (ref "U1") (pin "13") (pinfunction "RTS_13") (pintype "input"))
    )
    (net (code "74") (name "unconnected-(U1-SCL-Pad39)") (class "Default")
      (node (ref "U1") (pin "39") (pinfunction "SCL_39") (pintype "input"))
    )
    (net (code "75") (name "unconnected-(U1-SDA-Pad38)") (class "Default")
      (node (ref "U1") (pin "38") (pinfunction "SDA_38") (pintype "bidirectional"))
    )
    (net (code "76") (name "unconnected-(U1-SIM_DET-Pad33)") (class "Default")
      (node (ref "U1") (pin "33") (pinfunction "SIM_DET_33") (pintype "input"))
    )
    (net (code "77") (name "unconnected-(U1-SPK1N-Pad22)") (class "Default")
      (node (ref "U1") (pin "22") (pinfunction "SPK1N_22") (pintype "output"))
    )
    (net (code "78") (name "unconnected-(U1-SPK1P-Pad21)") (class "Default")
      (node (ref "U1") (pin "21") (pinfunction "SPK1P_21") (pintype "output"))
    )
    (net (code "79") (name "unconnected-(U1-USB_DN-Pad27)") (class "Default")
      (node (ref "U1") (pin "27") (pinfunction "USB_DN_27") (pintype "bidirectional"))
    )
    (net (code "80") (name "unconnected-(U1-USB_DP-Pad26)") (class "Default")
      (node (ref "U1") (pin "26") (pinfunction "USB_DP_26") (pintype "bidirectional"))
    )
    (net (code "81") (name "unconnected-(U1-VCHG-Pad25)") (class "Default")
      (node (ref "U1") (pin "25") (pinfunction "VCHG_25") (pintype "input"))
    )
    (net (code "82") (name "unconnected-(U1-VRTC-Pad17)") (class "Default")
      (node (ref "U1") (pin "17") (pinfunction "VRTC_17") (pintype "bidirectional"))
    )
    (net (code "83") (name "unconnected-(U1-~{RESET}-Pad16)") (class "Default")
      (node (ref "U1") (pin "16") (pinfunction "~{RESET}_16") (pintype "input"))
    )
    (net (code "84") (name "unconnected-(U2-PA0_WKUP-Pad10)") (class "Default")
      (node (ref "U2") (pin "10") (pinfunction "PA0_WKUP_10") (pintype "bidirectional"))
    )
    (net (code "85") (name "unconnected-(U2-PA1-Pad11)") (class "Default")
      (node (ref "U2") (pin "11") (pinfunction "PA1_11") (pintype "bidirectional"))
    )
    (net (code "86") (name "unconnected-(U2-PA2-Pad12)") (class "Default")
      (node (ref "U2") (pin "12") (pinfunction "PA2_12") (pintype "bidirectional"))
    )
    (net (code "87") (name "unconnected-(U2-PA3-Pad13)") (class "Default")
      (node (ref "U2") (pin "13") (pinfunction "PA3_13") (pintype "bidirectional"))
    )
    (net (code "88") (name "unconnected-(U2-PA4-Pad14)") (class "Default")
      (node (ref "U2") (pin "14") (pinfunction "PA4_14") (pintype "bidirectional"))
    )
    (net (code "89") (name "unconnected-(U2-PA5-Pad15)") (class "Default")
      (node (ref "U2") (pin "15") (pinfunction "PA5_15") (pintype "bidirectional"))
    )
    (net (code "90") (name "unconnected-(U2-PA6-Pad16)") (class "Default")
      (node (ref "U2") (pin "16") (pinfunction "PA6_16") (pintype "bidirectional"))
    )
    (net (code "91") (name "unconnected-(U2-PA7-Pad17)") (class "Default")
      (node (ref "U2") (pin "17") (pinfunction "PA7_17") (pintype "bidirectional"))
    )
    (net (code "92") (name "unconnected-(U2-PA11-Pad32)") (class "Default")
      (node (ref "U2") (pin "32") (pinfunction "PA11_32") (pintype "bidirectional"))
    )
    (net (code "93") (name "unconnected-(U2-PA12-Pad33)") (class "Default")
      (node (ref "U2") (pin "33") (pinfunction "PA12_33") (pintype "bidirectional"))
    )
    (net (code "94") (name "unconnected-(U2-PA15-Pad38)") (class "Default")
      (node (ref "U2") (pin "38") (pinfunction "PA15_38") (pintype "bidirectional"))
    )
    (net (code "95") (name "unconnected-(U2-PB0-Pad18)") (class "Default")
      (node (ref "U2") (pin "18") (pinfunction "PB0_18") (pintype "bidirectional"))
    )
    (net (code "96") (name "unconnected-(U2-PB1-Pad19)") (class "Default")
      (node (ref "U2") (pin "19") (pinfunction "PB1_19") (pintype "bidirectional"))
    )
    (net (code "97") (name "unconnected-(U2-PB2-Pad20)") (class "Default")
      (node (ref "U2") (pin "20") (pinfunction "PB2_20") (pintype "bidirectional"))
    )
    (net (code "98") (name "unconnected-(U2-PB3-Pad39)") (class "Default")
      (node (ref "U2") (pin "39") (pinfunction "PB3_39") (pintype "bidirectional"))
    )
    (net (code "99") (name "unconnected-(U2-PB4-Pad40)") (class "Default")
      (node (ref "U2") (pin "40") (pinfunction "PB4_40") (pintype "bidirectional"))
    )
    (net (code "100") (name "unconnected-(U2-PB5-Pad41)") (class "Default")
      (node (ref "U2") (pin "41") (pinfunction "PB5_41") (pintype "bidirectional"))
    )
    (net (code "101") (name "unconnected-(U2-PB8-Pad45)") (class "Default")
      (node (ref "U2") (pin "45") (pinfunction "PB8_45") (pintype "bidirectional"))
    )
    (net (code "102") (name "unconnected-(U2-PB9-Pad46)") (class "Default")
      (node (ref "U2") (pin "46") (pinfunction "PB9_46") (pintype "bidirectional"))
    )
    (net (code "103") (name "unconnected-(U2-PB10-Pad21)") (class "Default")
      (node (ref "U2") (pin "21") (pinfunction "PB10_21") (pintype "bidirectional"))
    )
    (net (code "104") (name "unconnected-(U2-PB11-Pad22)") (class "Default")
      (node (ref "U2") (pin "22") (pinfunction "PB11_22") (pintype "bidirectional"))
    )
    (net (code "105") (name "unconnected-(U2-PB12-Pad25)") (class "Default")
      (node (ref "U2") (pin "25") (pinfunction "PB12_25") (pintype "bidirectional"))
    )
    (net (code "106") (name "unconnected-(U2-PB13-Pad26)") (class "Default")
      (node (ref "U2") (pin "26") (pinfunction "PB13_26") (pintype "bidirectional"))
    )
    (net (code "107") (name "unconnected-(U2-PB14-Pad27)") (class "Default")
      (node (ref "U2") (pin "27") (pinfunction "PB14_27") (pintype "bidirectional"))
    )
    (net (code "108") (name "unconnected-(U2-PB15-Pad28)") (class "Default")
      (node (ref "U2") (pin "28") (pinfunction "PB15_28") (pintype "bidirectional"))
    )
    (net (code "109") (name "unconnected-(U2-PC14-OSC32_IN-Pad3)") (class "Default")
      (node (ref "U2") (pin "3") (pinfunction "PC14-OSC32_IN_3") (pintype "bidirectional"))
    )
    (net (code "110") (name "unconnected-(U2-PC15-OSC32_OUT-Pad4)") (class "Default")
      (node (ref "U2") (pin "4") (pinfunction "PC15-OSC32_OUT_4") (pintype "bidirectional"))
    )
    (net (code "111") (name "unconnected-(U2-VBAT-Pad1)") (class "Default")
      (node (ref "U2") (pin "1") (pinfunction "VBAT_1") (pintype "bidirectional"))
    )
    (net (code "112") (name "unconnected-(U3-GND-Pad8)") (class "Default")
      (node (ref "U3") (pin "8") (pinfunction "GND_8") (pintype "passive"))
    )
    (net (code "113") (name "unconnected-(U3-PRENSENCE-Pad4)") (class "Default")
      (node (ref "U3") (pin "4") (pinfunction "PRENSENCE_4") (pintype "passive"))
    )
    (net (code "114") (name "unconnected-(U3-VPP-Pad6)") (class "Default")
      (node (ref "U3") (pin "6") (pinfunction "VPP_6") (pintype "passive"))
    )
  )
)
